# SCH_lab06_2021-12-24.net
KiCad netlist of a schematic drawn in EasyEDA
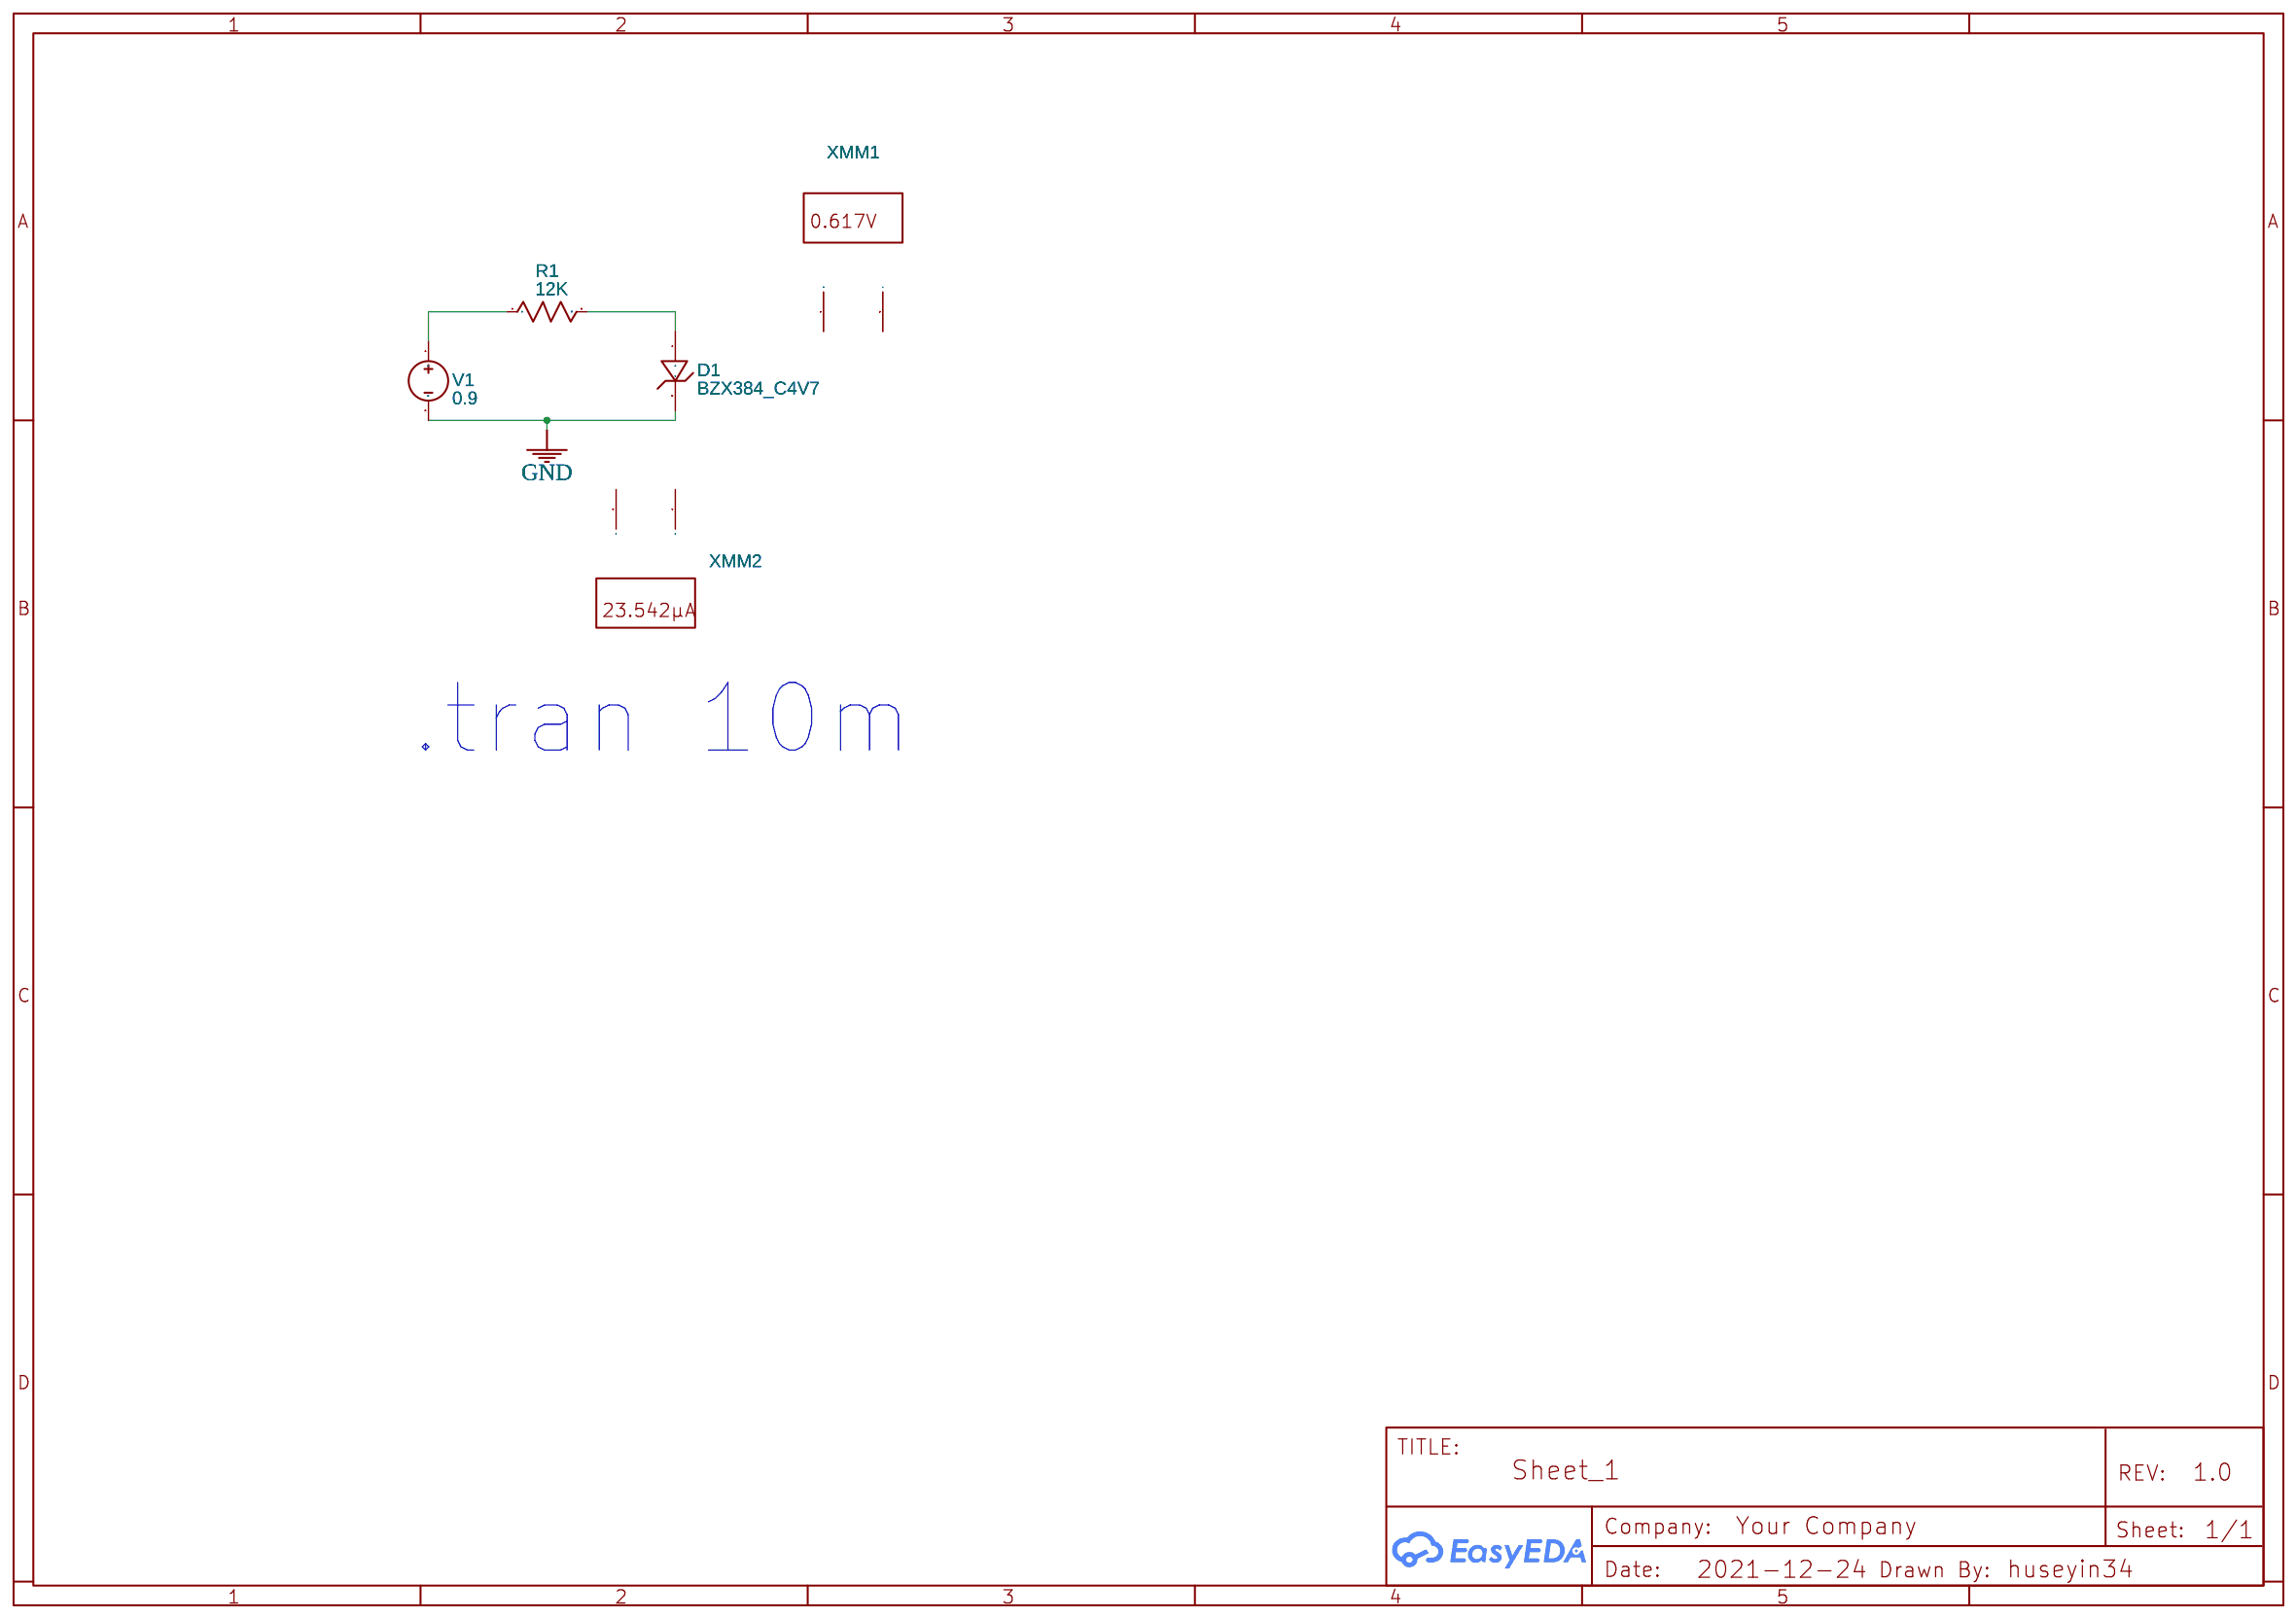
[diagram p0: circuit_1]
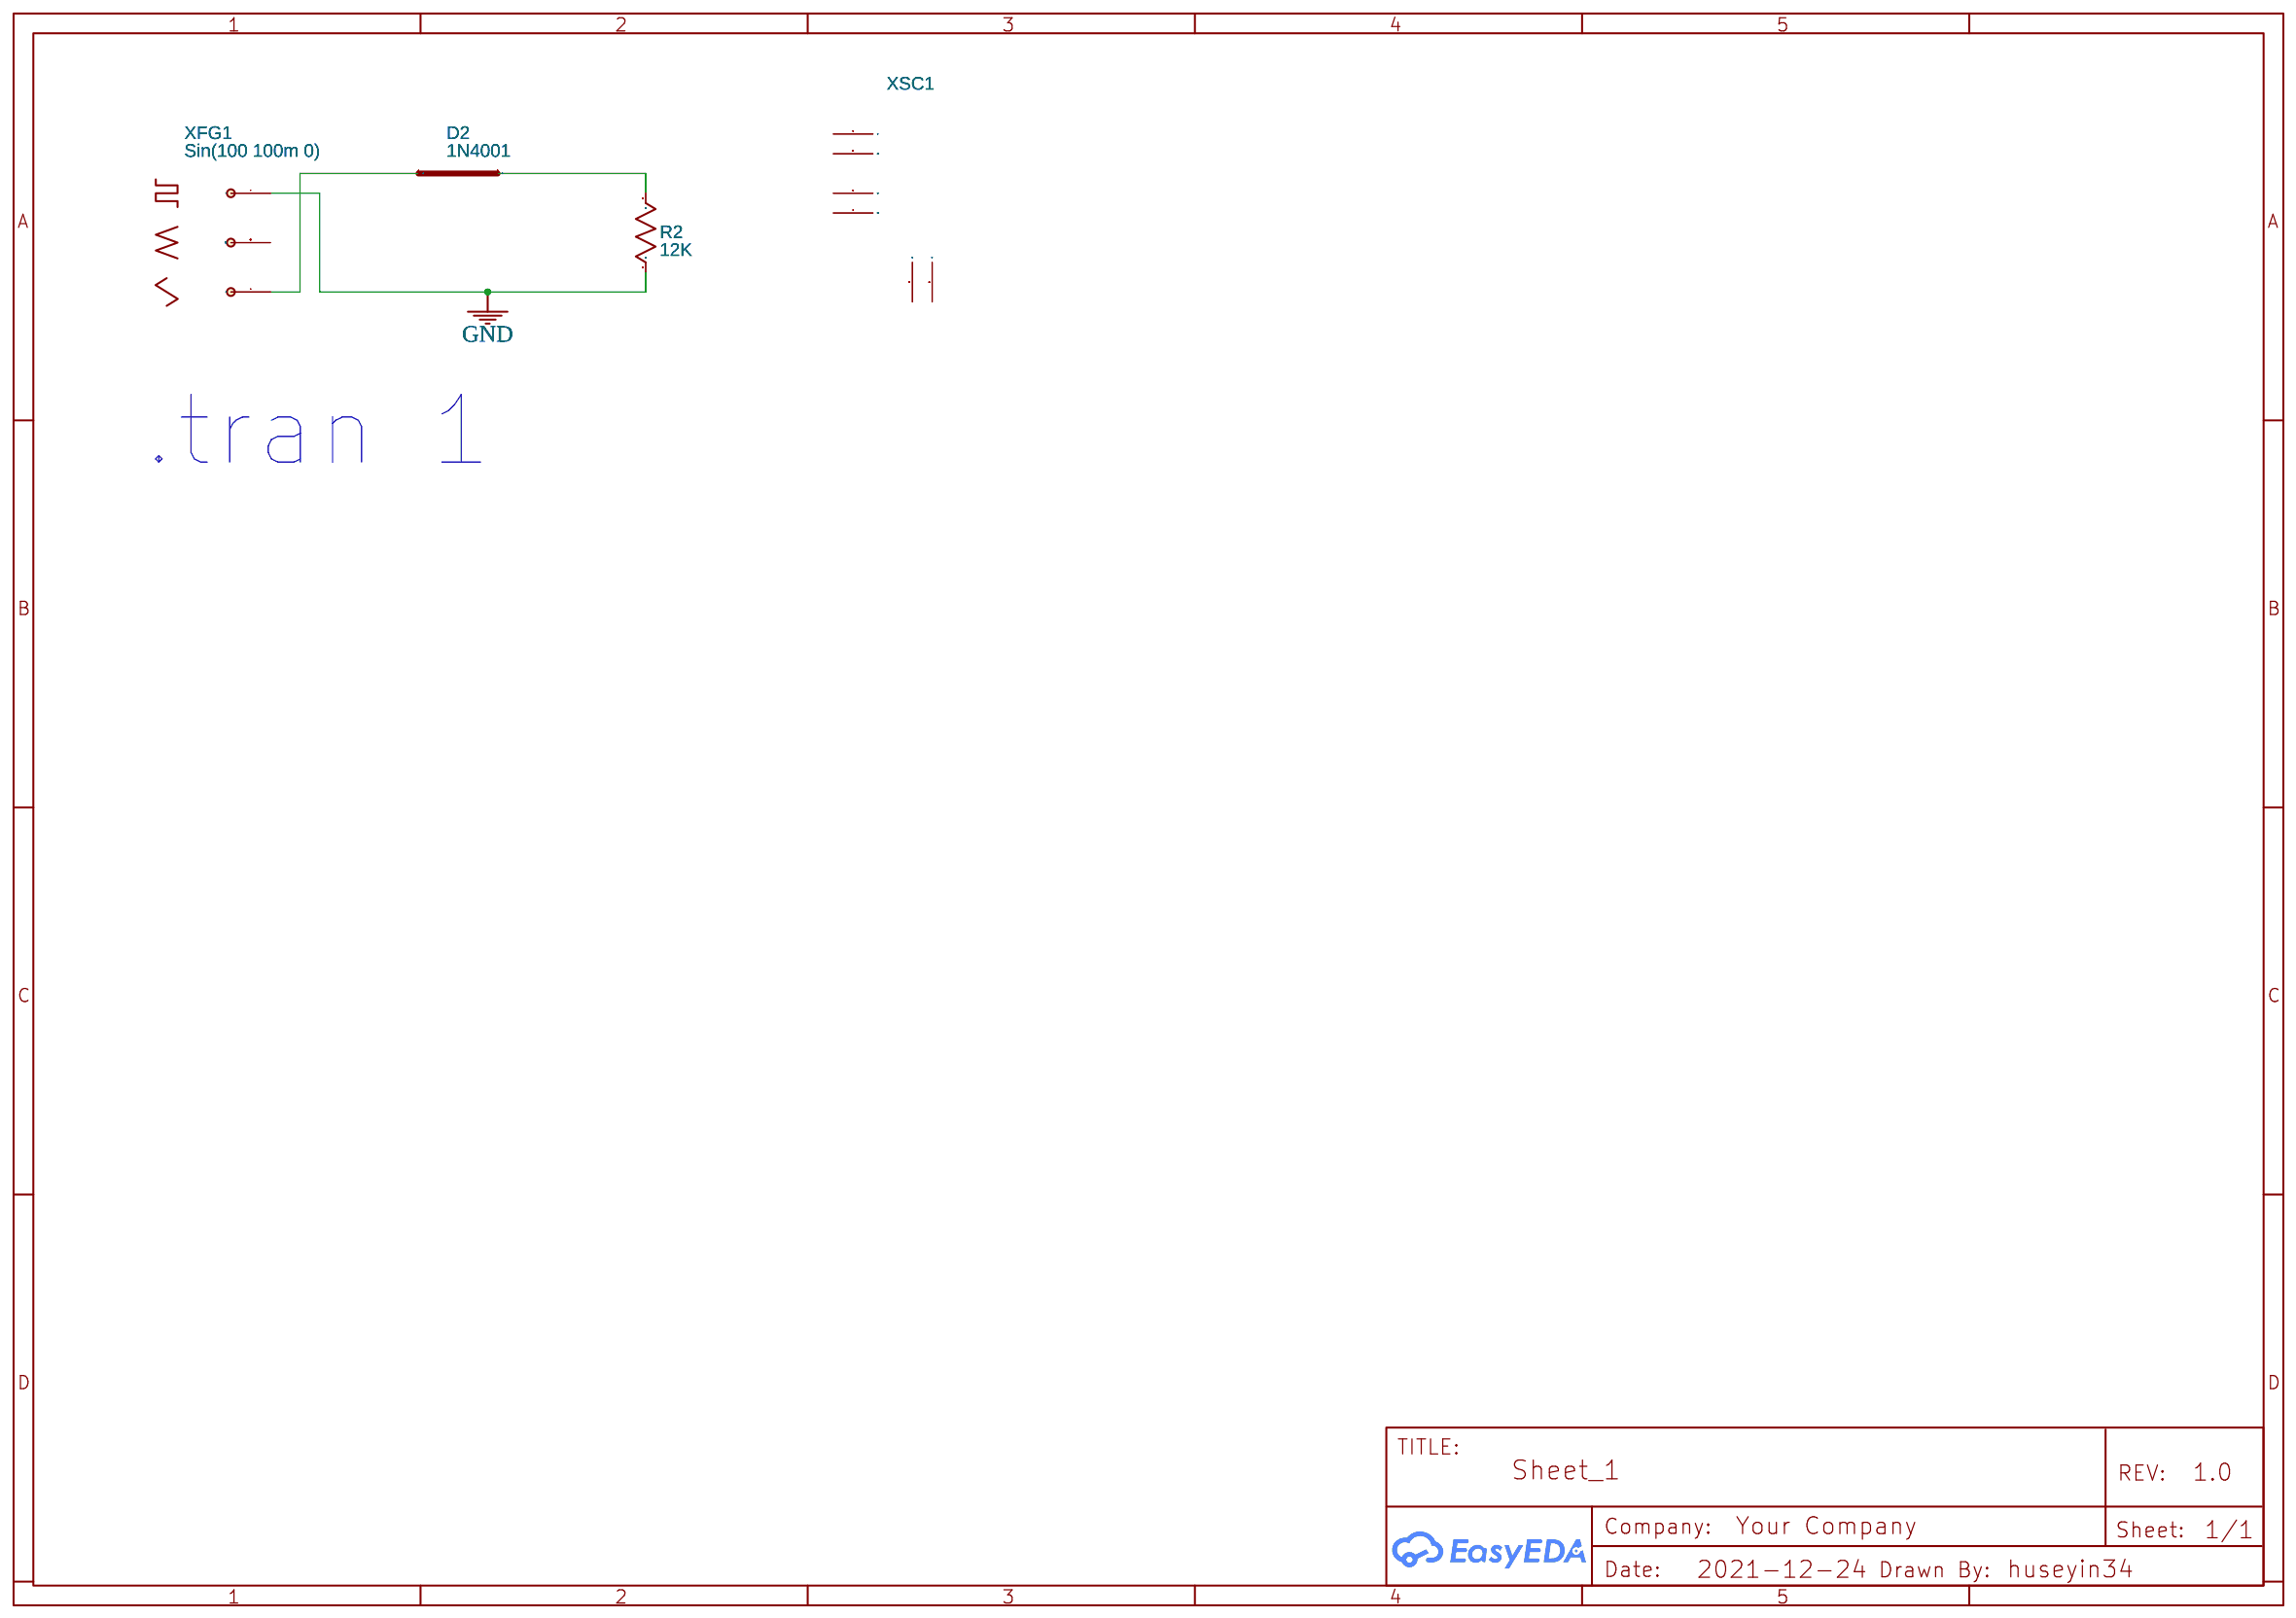
[diagram p1: circuit_2.1]
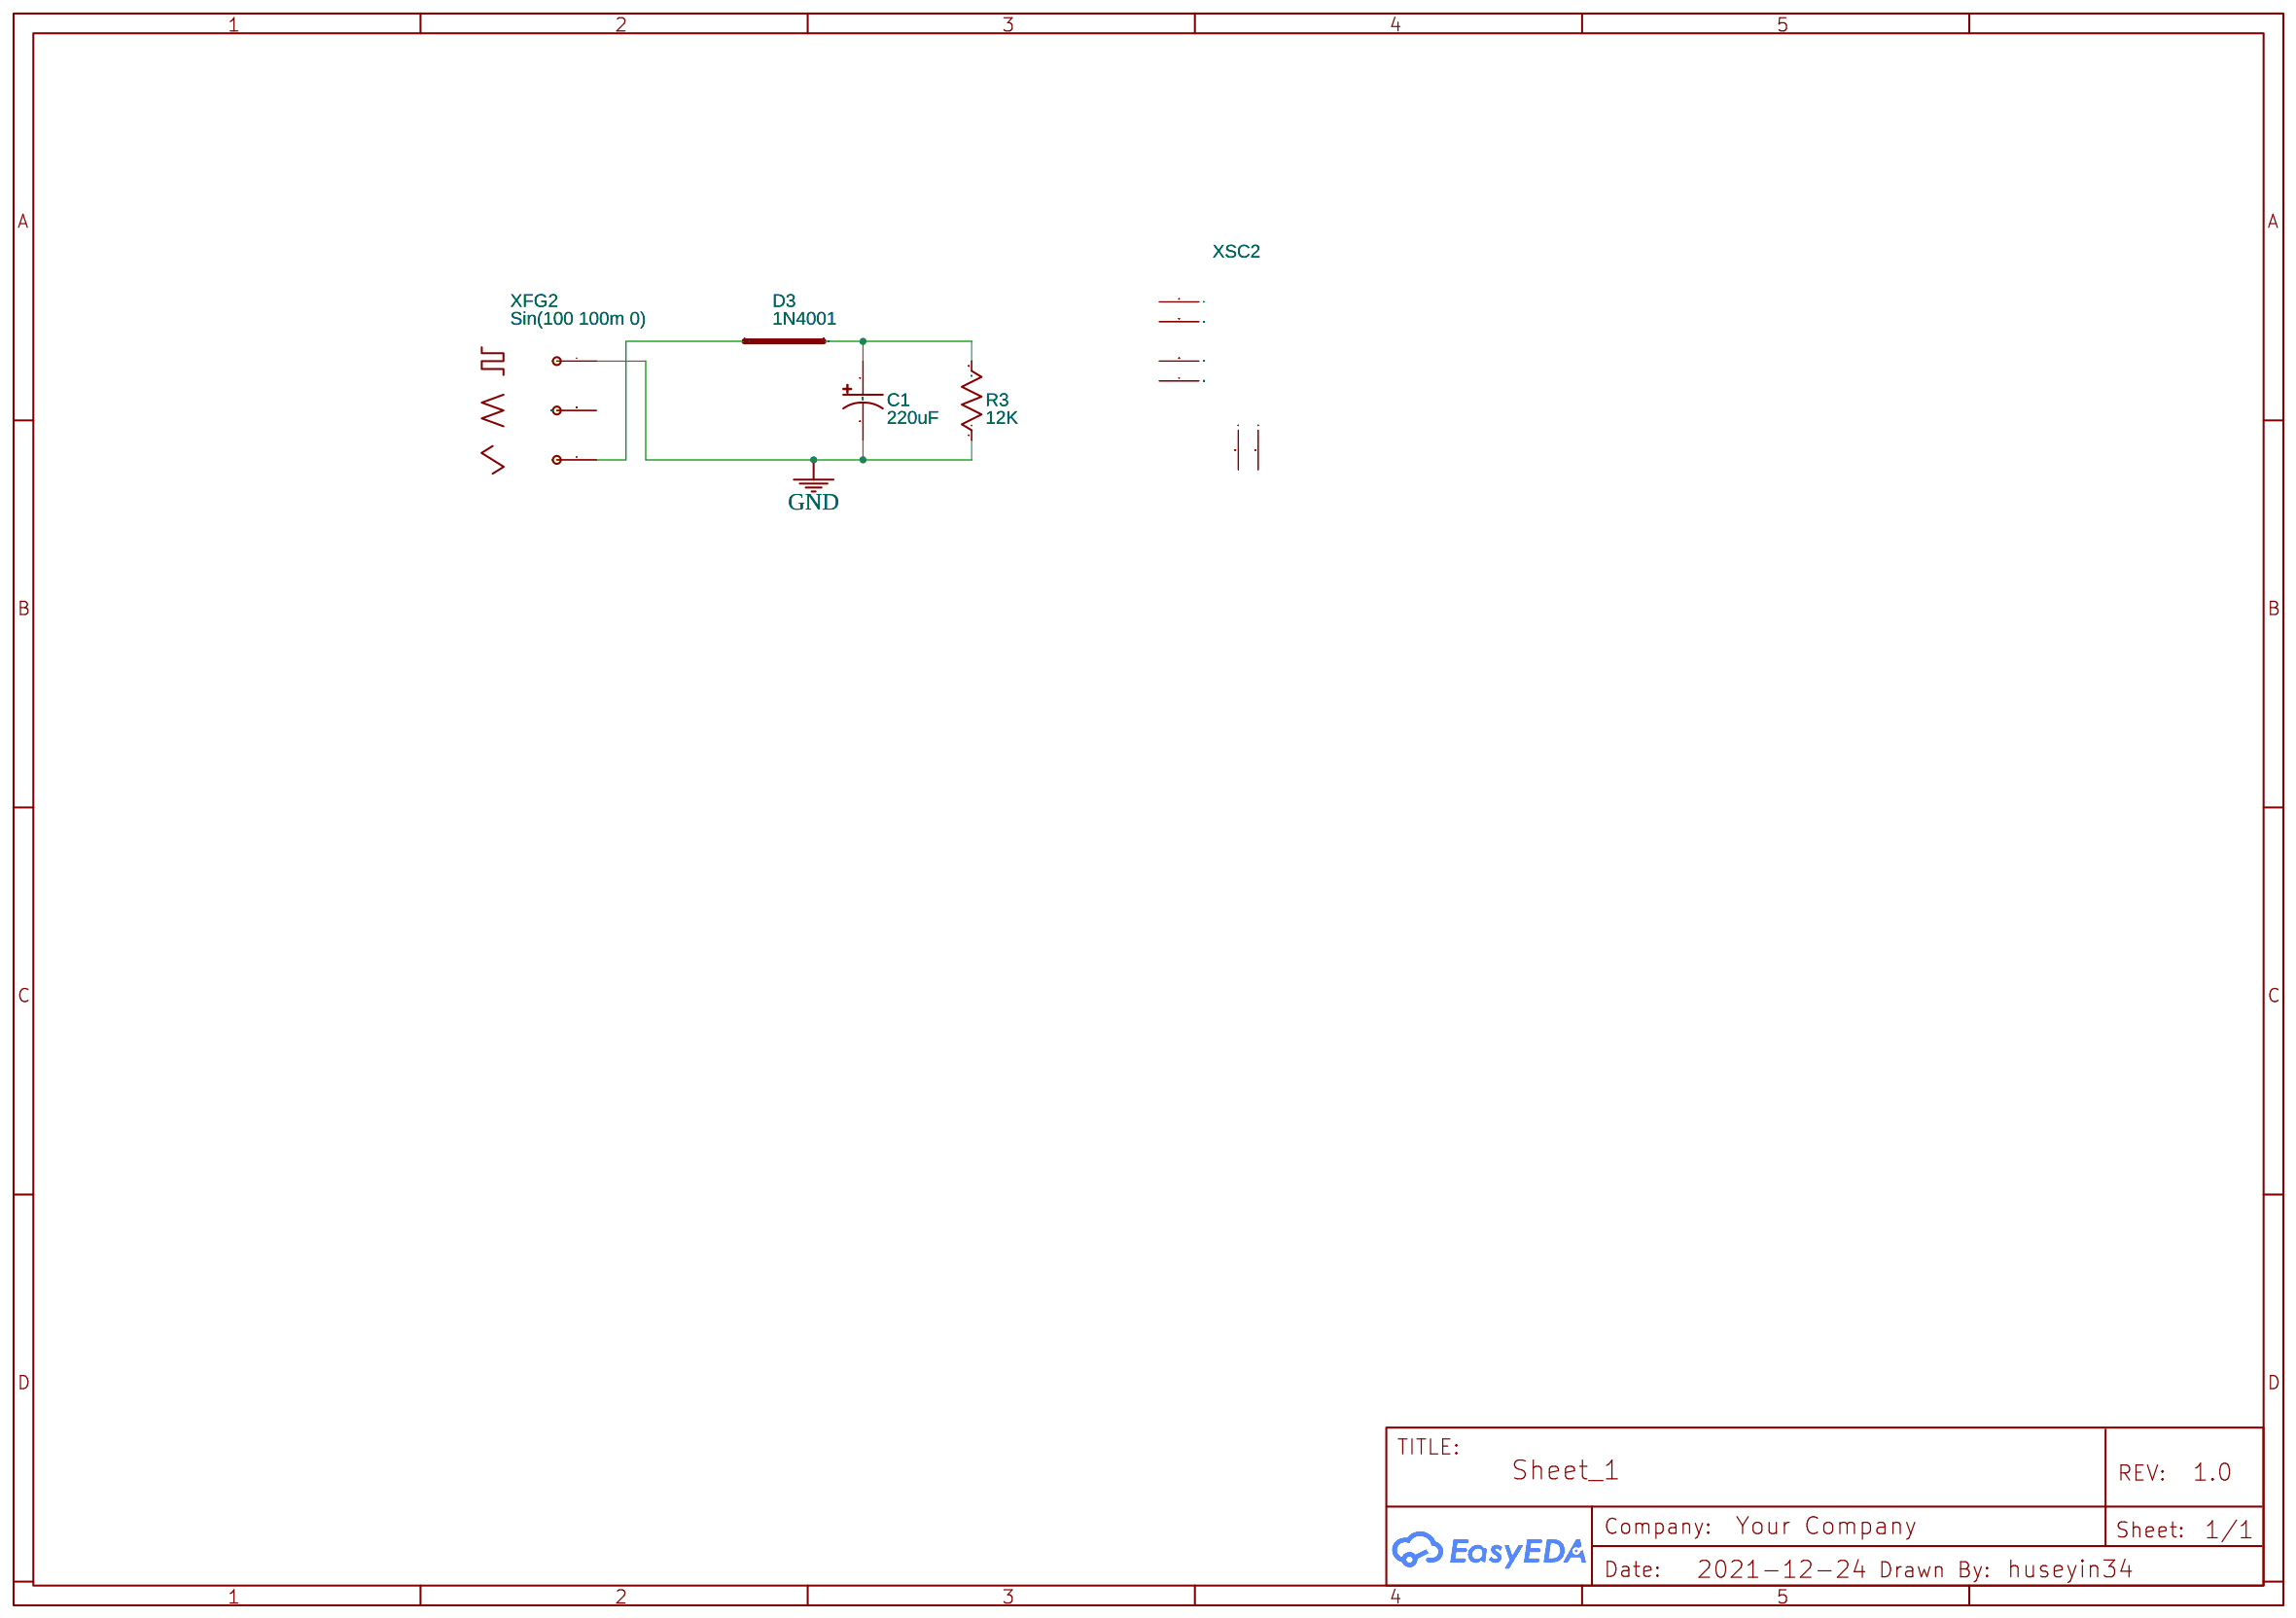
[diagram p2: circuit_2.2]

(export (version "E")
  (design (tool "Eeschema 10.0.6"))
  (components
    (comp (ref "D1") (value "BZX384_C4V7") (libsource (lib "") (part "BZX84C10L")))
    (comp (ref "R1") (value "12K") (libsource (lib "") (part "Resistor_US")))
    (comp (ref "V1") (value "0.9") (libsource (lib "") (part "VDC")))
    (comp (ref "XMM1") (value "Multimeter") (libsource (lib "") (part "MULTIMETER")))
    (comp (ref "XMM2") (value "Multimeter") (libsource (lib "") (part "MULTIMETER_1")))
    (comp (ref "D2") (value "1N4001") (libsource (lib "") (part "1N4001")))
    (comp (ref "R2") (value "12K") (libsource (lib "") (part "Resistor_US")))
    (comp (ref "XFG1") (value "Sin(100 100m 0)") (libsource (lib "") (part "FUNCTIONGENERATOR")))
    (comp (ref "XSC1") (value "Oscilloscope") (libsource (lib "") (part "OSCILLOSCOPE")))
    (comp (ref "C1") (value "220uF") (libsource (lib "") (part "Capacitor_Electrolytic_US")))
    (comp (ref "D3") (value "1N4001") (libsource (lib "") (part "1N4001")))
    (comp (ref "R3") (value "12K") (libsource (lib "") (part "Resistor_US")))
    (comp (ref "XFG2") (value "Sin(100 100m 0)") (libsource (lib "") (part "FUNCTIONGENERATOR")))
    (comp (ref "XSC2") (value "Oscilloscope") (libsource (lib "") (part "OSCILLOSCOPE")))
  )
  (nets
    (net (code "1") (name "GND") (class "Default")
      (node (ref "C1") (pin "2") (pinfunction "2_2") (pintype "unspecified"))
      (node (ref "D1") (pin "2") (pinfunction "K_2") (pintype "unspecified"))
      (node (ref "R2") (pin "1") (pinfunction "1_1") (pintype "unspecified"))
      (node (ref "R3") (pin "1") (pinfunction "1_1") (pintype "unspecified"))
      (node (ref "V1") (pin "2") (pinfunction "2_2") (pintype "unspecified"))
      (node (ref "XFG1") (pin "-") (pinfunction "-_-") (pintype "unspecified"))
      (node (ref "XFG2") (pin "-") (pinfunction "-_-") (pintype "unspecified"))
    )
    (net (code "2") (name "Net-(C1-Pad1)") (class "Default")
      (node (ref "C1") (pin "1") (pinfunction "1_1") (pintype "unspecified"))
      (node (ref "D3") (pin "2") (pinfunction "2_2") (pintype "unspecified"))
      (node (ref "R3") (pin "2") (pinfunction "2_2") (pintype "unspecified"))
    )
    (net (code "3") (name "Net-(D1-A)") (class "Default")
      (node (ref "D1") (pin "1") (pinfunction "A_1") (pintype "unspecified"))
      (node (ref "R1") (pin "2") (pinfunction "2_2") (pintype "unspecified"))
    )
    (net (code "4") (name "Net-(D2-Pad1)") (class "Default")
      (node (ref "D2") (pin "1") (pinfunction "1_1") (pintype "unspecified"))
      (node (ref "XFG1") (pin "+") (pinfunction "+_+") (pintype "unspecified"))
    )
    (net (code "5") (name "Net-(D2-Pad2)") (class "Default")
      (node (ref "D2") (pin "2") (pinfunction "2_2") (pintype "unspecified"))
      (node (ref "R2") (pin "2") (pinfunction "2_2") (pintype "unspecified"))
    )
    (net (code "6") (name "Net-(D3-Pad1)") (class "Default")
      (node (ref "D3") (pin "1") (pinfunction "1_1") (pintype "unspecified"))
      (node (ref "XFG2") (pin "+") (pinfunction "+_+") (pintype "unspecified"))
    )
    (net (code "7") (name "Net-(R1-Pad1)") (class "Default")
      (node (ref "R1") (pin "1") (pinfunction "1_1") (pintype "unspecified"))
      (node (ref "V1") (pin "1") (pinfunction "1_1") (pintype "unspecified"))
    )
    (net (code "8") (name "unconnected-(XFG1-PadCOM)") (class "Default")
      (node (ref "XFG1") (pin "COM") (pinfunction "COM_COM") (pintype "unspecified"))
    )
    (net (code "9") (name "unconnected-(XFG2-PadCOM)") (class "Default")
      (node (ref "XFG2") (pin "COM") (pinfunction "COM_COM") (pintype "unspecified"))
    )
    (net (code "10") (name "unconnected-(XMM1-+-Pad1)") (class "Default")
      (node (ref "XMM1") (pin "1") (pinfunction "+_1") (pintype "unspecified"))
    )
    (net (code "11") (name "unconnected-(XMM1-I-Pad2)") (class "Default")
      (node (ref "XMM1") (pin "2") (pinfunction "I_2") (pintype "unspecified"))
    )
    (net (code "12") (name "unconnected-(XMM2-+-Pad1)") (class "Default")
      (node (ref "XMM2") (pin "1") (pinfunction "+_1") (pintype "unspecified"))
    )
    (net (code "13") (name "unconnected-(XMM2-I-Pad2)") (class "Default")
      (node (ref "XMM2") (pin "2") (pinfunction "I_2") (pintype "unspecified"))
    )
    (net (code "14") (name "unconnected-(XSC1-A-Pad1)") (class "Default")
      (node (ref "XSC1") (pin "1") (pinfunction "A_1") (pintype "unspecified"))
    )
    (net (code "15") (name "unconnected-(XSC1-B-Pad3)") (class "Default")
      (node (ref "XSC1") (pin "3") (pinfunction "B_3") (pintype "unspecified"))
    )
    (net (code "16") (name "unconnected-(XSC1-GND1-Pad2)") (class "Default")
      (node (ref "XSC1") (pin "2") (pinfunction "GND1_2") (pintype "unspecified"))
    )
    (net (code "17") (name "unconnected-(XSC1-GND2-Pad4)") (class "Default")
      (node (ref "XSC1") (pin "4") (pinfunction "GND2_4") (pintype "unspecified"))
    )
    (net (code "18") (name "unconnected-(XSC1-T+-Pad5)") (class "Default")
      (node (ref "XSC1") (pin "5") (pinfunction "T+_5") (pintype "unspecified"))
    )
    (net (code "19") (name "unconnected-(XSC1-T--Pad6)") (class "Default")
      (node (ref "XSC1") (pin "6") (pinfunction "T-_6") (pintype "unspecified"))
    )
    (net (code "20") (name "unconnected-(XSC2-A-Pad1)") (class "Default")
      (node (ref "XSC2") (pin "1") (pinfunction "A_1") (pintype "unspecified"))
    )
    (net (code "21") (name "unconnected-(XSC2-B-Pad3)") (class "Default")
      (node (ref "XSC2") (pin "3") (pinfunction "B_3") (pintype "unspecified"))
    )
    (net (code "22") (name "unconnected-(XSC2-GND1-Pad2)") (class "Default")
      (node (ref "XSC2") (pin "2") (pinfunction "GND1_2") (pintype "unspecified"))
    )
    (net (code "23") (name "unconnected-(XSC2-GND2-Pad4)") (class "Default")
      (node (ref "XSC2") (pin "4") (pinfunction "GND2_4") (pintype "unspecified"))
    )
    (net (code "24") (name "unconnected-(XSC2-T+-Pad5)") (class "Default")
      (node (ref "XSC2") (pin "5") (pinfunction "T+_5") (pintype "unspecified"))
    )
    (net (code "25") (name "unconnected-(XSC2-T--Pad6)") (class "Default")
      (node (ref "XSC2") (pin "6") (pinfunction "T-_6") (pintype "unspecified"))
    )
  )
)
